# FPGA-Connector.net
KiCad netlist of a schematic drawn in Altium Designer
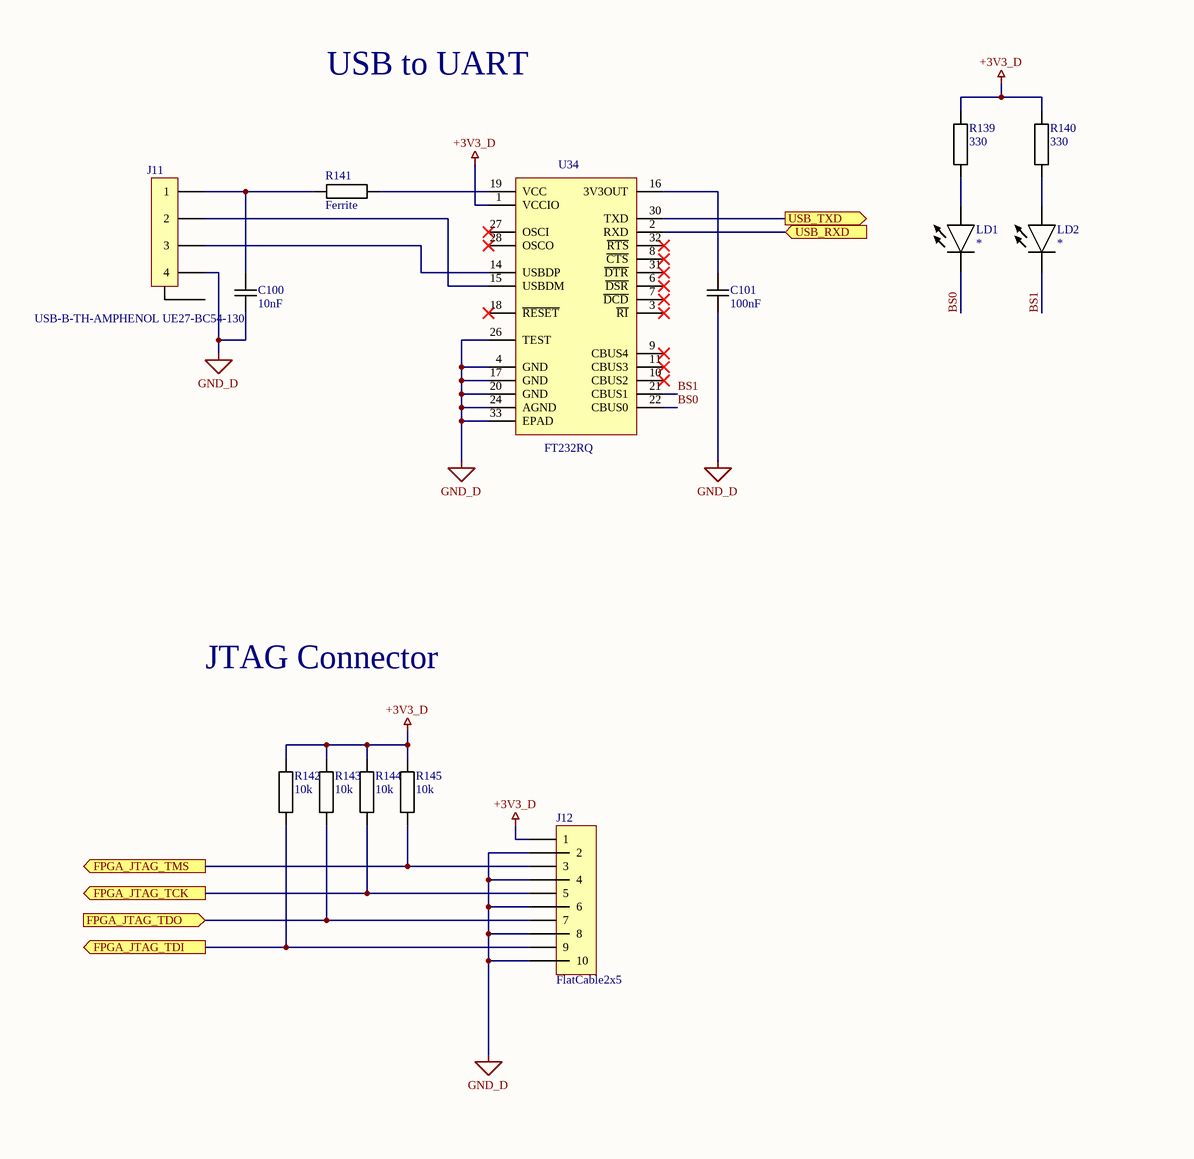
[diagram p0: FPGA-Connector.SchDoc, left]
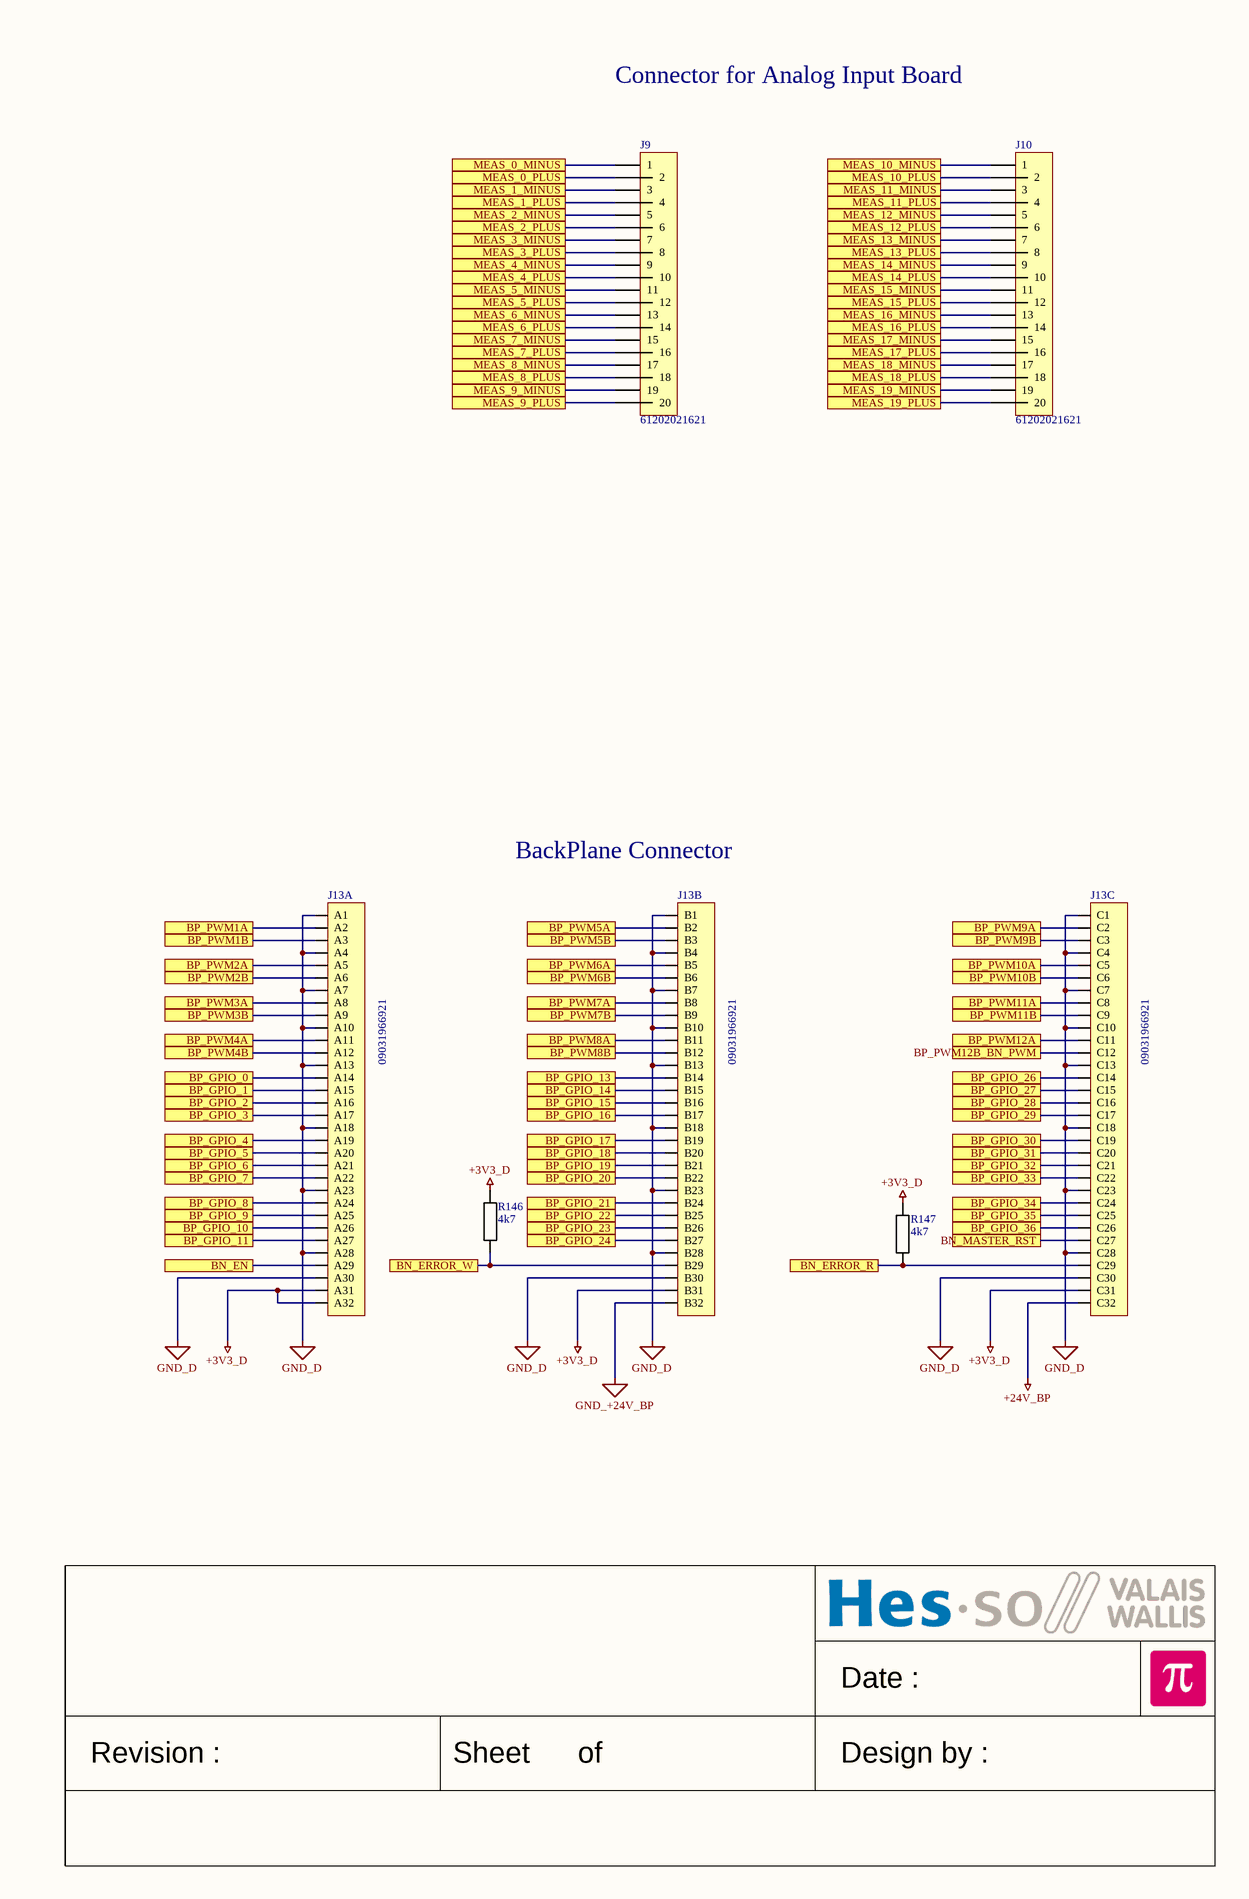
[diagram p1: FPGA-Connector.SchDoc, right]

(export (version "E")
  (design (tool "Eeschema 10.0.6"))
  (components
    (comp (ref "C100")
      (value "10nF")
      (footprint "CAPACITOR 1608 REFLOW")
      (description "Capacitor X7R 10% 50V 1608(0603)")
      (libsource (lib "Capacitor") (part "Capacitor"))
    )
    (comp (ref "C101")
      (value "100nF")
      (footprint "CAPACITOR 1608 REFLOW")
      (description "Capacitor X7R 10% 50V 1608(0603)")
      (libsource (lib "Capacitor") (part "Capacitor"))
    )
    (comp (ref "J9")
      (value "61202021621")
      (footprint "FlatCable2x10 2.54MM Straight TH")
      (description "FlatCable2x10")
      (fields (field (name "MANUFACTURER") "Wurth Elektronik"))
      (libsource (lib "Connector") (part "FlatCable2x10"))
    )
    (comp (ref "J10")
      (value "61202021621")
      (footprint "FlatCable2x10 2.54MM Straight TH")
      (description "FlatCable2x10")
      (fields (field (name "MANUFACTURER") "Wurth Elektronik"))
      (libsource (lib "Connector") (part "FlatCable2x10"))
    )
    (comp (ref "J11")
      (value "USB-B-TH-AMPHENOL UE27-BC54-130")
      (footprint "USB-B TH AMPHENOL UE27-BC54-130")
      (libsource (lib "Connector") (part "USB-B-TH-AMPHENOL UE27-BC54-130"))
    )
    (comp (ref "J12")
      (value "FlatCable2x5")
      (footprint "FlatCable2x5 2MM Straight TH FCI 98414-G06-10ULF")
      (libsource (lib "Connector") (part "FlatCable2x5"))
    )
    (comp (ref "J13")
      (value "09031966921")
      (footprint "DIN41612 MALE 3X32 ABC R90")
      (description "DIN41612 MALE 3X32 ABC R90")
      (fields (field (name "MANUFACTURER") "Harting"))
      (libsource (lib "Connector") (part "DIN41612 MALE 3X32 ABC R90"))
    )
    (comp (ref "LD1")
      (value "*")
      (footprint "LED 1608 REFLOW")
      (description "LED generic")
      (libsource (lib "Diode") (part "LED"))
    )
    (comp (ref "LD2")
      (value "*")
      (footprint "LED 1608 REFLOW")
      (description "LED generic")
      (libsource (lib "Diode") (part "LED"))
    )
    (comp (ref "R139")
      (value "330")
      (footprint "RESISTOR 2012 REFLOW")
      (description "Resistor 1% 50V 125mW 2012(0805)")
      (libsource (lib "Resistor") (part "Resistor"))
    )
    (comp (ref "R140")
      (value "330")
      (footprint "RESISTOR 2012 REFLOW")
      (description "Resistor 1% 50V 125mW 2012(0805)")
      (libsource (lib "Resistor") (part "Resistor"))
    )
    (comp (ref "R141")
      (value "Ferrite")
      (footprint "RESISTOR 1608 REFLOW")
      (description "Resistor 1% 50V 100mW 1608(0603)")
      (libsource (lib "Resistor") (part "Resistor"))
    )
    (comp (ref "R142")
      (value "10k")
      (footprint "RESISTOR 1608 REFLOW")
      (description "Resistor 1% 50V 100mW 1608(0603)")
      (libsource (lib "Resistor") (part "Resistor"))
    )
    (comp (ref "R143")
      (value "10k")
      (footprint "RESISTOR 1608 REFLOW")
      (description "Resistor 1% 50V 100mW 1608(0603)")
      (libsource (lib "Resistor") (part "Resistor"))
    )
    (comp (ref "R144")
      (value "10k")
      (footprint "RESISTOR 1608 REFLOW")
      (description "Resistor 1% 50V 100mW 1608(0603)")
      (libsource (lib "Resistor") (part "Resistor"))
    )
    (comp (ref "R145")
      (value "10k")
      (footprint "RESISTOR 1608 REFLOW")
      (description "Resistor 1% 50V 100mW 1608(0603)")
      (libsource (lib "Resistor") (part "Resistor"))
    )
    (comp (ref "R146")
      (value "4k7")
      (footprint "RESISTOR 1608 REFLOW")
      (description "Resistor 1% 50V 100mW 1608(0603)")
      (libsource (lib "Resistor") (part "Resistor"))
    )
    (comp (ref "R147")
      (value "4k7")
      (footprint "RESISTOR 1608 REFLOW")
      (description "Resistor 1% 50V 100mW 1608(0603)")
      (libsource (lib "Resistor") (part "Resistor"))
    )
    (comp (ref "U34")
      (value "FT232RQ")
      (footprint "QFN32 P0.5 T3.2x3.2 C5.0X5.0 H1.0")
      (description "24-Bit ADC with Ultra Low Noise PGIA - Crystal")
      (libsource (lib "IntegratedCircuit - Copy") (part "FT232RQ"))
    )
  )
  (nets
    (net (code "1") (name "+3V3_D") (class "Default")
      (node (ref "J12") (pin "1") (pinfunction "1_1") (pintype "passive"))
      (node (ref "J13") (pin "A31") (pinfunction "A31_A31") (pintype "passive"))
      (node (ref "J13") (pin "A32") (pinfunction "A32_A32") (pintype "passive"))
      (node (ref "J13") (pin "B31") (pinfunction "B31_B31") (pintype "passive"))
      (node (ref "J13") (pin "C31") (pinfunction "C31_C31") (pintype "passive"))
      (node (ref "R139") (pin "2") (pinfunction "2_2") (pintype "passive"))
      (node (ref "R140") (pin "2") (pinfunction "2_2") (pintype "passive"))
      (node (ref "R142") (pin "2") (pinfunction "2_2") (pintype "passive"))
      (node (ref "R143") (pin "2") (pinfunction "2_2") (pintype "passive"))
      (node (ref "R144") (pin "2") (pinfunction "2_2") (pintype "passive"))
      (node (ref "R145") (pin "2") (pinfunction "2_2") (pintype "passive"))
      (node (ref "R146") (pin "2") (pinfunction "2_2") (pintype "passive"))
      (node (ref "R147") (pin "2") (pinfunction "2_2") (pintype "passive"))
      (node (ref "U34") (pin "1") (pinfunction "VCCIO_1") (pintype "passive"))
    )
    (net (code "2") (name "+24V_BP") (class "Default")
      (node (ref "J13") (pin "C32") (pinfunction "C32_C32") (pintype "passive"))
    )
    (net (code "3") (name "/BN_EN") (class "Default")
      (node (ref "J13") (pin "A29") (pinfunction "A29_A29") (pintype "passive"))
    )
    (net (code "4") (name "/BN_ERROR_R") (class "Default")
      (node (ref "J13") (pin "C29") (pinfunction "C29_C29") (pintype "passive"))
      (node (ref "R147") (pin "1") (pinfunction "1_1") (pintype "passive"))
    )
    (net (code "5") (name "/BN_ERROR_W") (class "Default")
      (node (ref "J13") (pin "B29") (pinfunction "B29_B29") (pintype "passive"))
      (node (ref "R146") (pin "1") (pinfunction "1_1") (pintype "passive"))
    )
    (net (code "6") (name "/BN_MASTER_RST") (class "Default")
      (node (ref "J13") (pin "C27") (pinfunction "C27_C27") (pintype "passive"))
    )
    (net (code "7") (name "/BP_GPIO_0") (class "Default")
      (node (ref "J13") (pin "A14") (pinfunction "A14_A14") (pintype "passive"))
    )
    (net (code "8") (name "/BP_GPIO_1") (class "Default")
      (node (ref "J13") (pin "A15") (pinfunction "A15_A15") (pintype "passive"))
    )
    (net (code "9") (name "/BP_GPIO_2") (class "Default")
      (node (ref "J13") (pin "A16") (pinfunction "A16_A16") (pintype "passive"))
    )
    (net (code "10") (name "/BP_GPIO_3") (class "Default")
      (node (ref "J13") (pin "A17") (pinfunction "A17_A17") (pintype "passive"))
    )
    (net (code "11") (name "/BP_GPIO_4") (class "Default")
      (node (ref "J13") (pin "A19") (pinfunction "A19_A19") (pintype "passive"))
    )
    (net (code "12") (name "/BP_GPIO_5") (class "Default")
      (node (ref "J13") (pin "A20") (pinfunction "A20_A20") (pintype "passive"))
    )
    (net (code "13") (name "/BP_GPIO_6") (class "Default")
      (node (ref "J13") (pin "A21") (pinfunction "A21_A21") (pintype "passive"))
    )
    (net (code "14") (name "/BP_GPIO_7") (class "Default")
      (node (ref "J13") (pin "A22") (pinfunction "A22_A22") (pintype "passive"))
    )
    (net (code "15") (name "/BP_GPIO_8") (class "Default")
      (node (ref "J13") (pin "A24") (pinfunction "A24_A24") (pintype "passive"))
    )
    (net (code "16") (name "/BP_GPIO_9") (class "Default")
      (node (ref "J13") (pin "A25") (pinfunction "A25_A25") (pintype "passive"))
    )
    (net (code "17") (name "/BP_GPIO_10") (class "Default")
      (node (ref "J13") (pin "A26") (pinfunction "A26_A26") (pintype "passive"))
    )
    (net (code "18") (name "/BP_GPIO_11") (class "Default")
      (node (ref "J13") (pin "A27") (pinfunction "A27_A27") (pintype "passive"))
    )
    (net (code "19") (name "/BP_GPIO_13") (class "Default")
      (node (ref "J13") (pin "B14") (pinfunction "B14_B14") (pintype "passive"))
    )
    (net (code "20") (name "/BP_GPIO_14") (class "Default")
      (node (ref "J13") (pin "B15") (pinfunction "B15_B15") (pintype "passive"))
    )
    (net (code "21") (name "/BP_GPIO_15") (class "Default")
      (node (ref "J13") (pin "B16") (pinfunction "B16_B16") (pintype "passive"))
    )
    (net (code "22") (name "/BP_GPIO_16") (class "Default")
      (node (ref "J13") (pin "B17") (pinfunction "B17_B17") (pintype "passive"))
    )
    (net (code "23") (name "/BP_GPIO_17") (class "Default")
      (node (ref "J13") (pin "B19") (pinfunction "B19_B19") (pintype "passive"))
    )
    (net (code "24") (name "/BP_GPIO_18") (class "Default")
      (node (ref "J13") (pin "B20") (pinfunction "B20_B20") (pintype "passive"))
    )
    (net (code "25") (name "/BP_GPIO_19") (class "Default")
      (node (ref "J13") (pin "B21") (pinfunction "B21_B21") (pintype "passive"))
    )
    (net (code "26") (name "/BP_GPIO_20") (class "Default")
      (node (ref "J13") (pin "B22") (pinfunction "B22_B22") (pintype "passive"))
    )
    (net (code "27") (name "/BP_GPIO_21") (class "Default")
      (node (ref "J13") (pin "B24") (pinfunction "B24_B24") (pintype "passive"))
    )
    (net (code "28") (name "/BP_GPIO_22") (class "Default")
      (node (ref "J13") (pin "B25") (pinfunction "B25_B25") (pintype "passive"))
    )
    (net (code "29") (name "/BP_GPIO_23") (class "Default")
      (node (ref "J13") (pin "B26") (pinfunction "B26_B26") (pintype "passive"))
    )
    (net (code "30") (name "/BP_GPIO_24") (class "Default")
      (node (ref "J13") (pin "B27") (pinfunction "B27_B27") (pintype "passive"))
    )
    (net (code "31") (name "/BP_GPIO_26") (class "Default")
      (node (ref "J13") (pin "C14") (pinfunction "C14_C14") (pintype "passive"))
    )
    (net (code "32") (name "/BP_GPIO_27") (class "Default")
      (node (ref "J13") (pin "C15") (pinfunction "C15_C15") (pintype "passive"))
    )
    (net (code "33") (name "/BP_GPIO_28") (class "Default")
      (node (ref "J13") (pin "C16") (pinfunction "C16_C16") (pintype "passive"))
    )
    (net (code "34") (name "/BP_GPIO_29") (class "Default")
      (node (ref "J13") (pin "C17") (pinfunction "C17_C17") (pintype "passive"))
    )
    (net (code "35") (name "/BP_GPIO_30") (class "Default")
      (node (ref "J13") (pin "C19") (pinfunction "C19_C19") (pintype "passive"))
    )
    (net (code "36") (name "/BP_GPIO_31") (class "Default")
      (node (ref "J13") (pin "C20") (pinfunction "C20_C20") (pintype "passive"))
    )
    (net (code "37") (name "/BP_GPIO_32") (class "Default")
      (node (ref "J13") (pin "C21") (pinfunction "C21_C21") (pintype "passive"))
    )
    (net (code "38") (name "/BP_GPIO_33") (class "Default")
      (node (ref "J13") (pin "C22") (pinfunction "C22_C22") (pintype "passive"))
    )
    (net (code "39") (name "/BP_GPIO_34") (class "Default")
      (node (ref "J13") (pin "C24") (pinfunction "C24_C24") (pintype "passive"))
    )
    (net (code "40") (name "/BP_GPIO_35") (class "Default")
      (node (ref "J13") (pin "C25") (pinfunction "C25_C25") (pintype "passive"))
    )
    (net (code "41") (name "/BP_GPIO_36") (class "Default")
      (node (ref "J13") (pin "C26") (pinfunction "C26_C26") (pintype "passive"))
    )
    (net (code "42") (name "/BP_PWM1A") (class "Default")
      (node (ref "J13") (pin "A2") (pinfunction "A2_A2") (pintype "passive"))
    )
    (net (code "43") (name "/BP_PWM1B") (class "Default")
      (node (ref "J13") (pin "A3") (pinfunction "A3_A3") (pintype "passive"))
    )
    (net (code "44") (name "/BP_PWM2A") (class "Default")
      (node (ref "J13") (pin "A5") (pinfunction "A5_A5") (pintype "passive"))
    )
    (net (code "45") (name "/BP_PWM2B") (class "Default")
      (node (ref "J13") (pin "A6") (pinfunction "A6_A6") (pintype "passive"))
    )
    (net (code "46") (name "/BP_PWM3A") (class "Default")
      (node (ref "J13") (pin "A8") (pinfunction "A8_A8") (pintype "passive"))
    )
    (net (code "47") (name "/BP_PWM3B") (class "Default")
      (node (ref "J13") (pin "A9") (pinfunction "A9_A9") (pintype "passive"))
    )
    (net (code "48") (name "/BP_PWM4A") (class "Default")
      (node (ref "J13") (pin "A11") (pinfunction "A11_A11") (pintype "passive"))
    )
    (net (code "49") (name "/BP_PWM4B") (class "Default")
      (node (ref "J13") (pin "A12") (pinfunction "A12_A12") (pintype "passive"))
    )
    (net (code "50") (name "/BP_PWM5A") (class "Default")
      (node (ref "J13") (pin "B2") (pinfunction "B2_B2") (pintype "passive"))
    )
    (net (code "51") (name "/BP_PWM5B") (class "Default")
      (node (ref "J13") (pin "B3") (pinfunction "B3_B3") (pintype "passive"))
    )
    (net (code "52") (name "/BP_PWM6A") (class "Default")
      (node (ref "J13") (pin "B5") (pinfunction "B5_B5") (pintype "passive"))
    )
    (net (code "53") (name "/BP_PWM6B") (class "Default")
      (node (ref "J13") (pin "B6") (pinfunction "B6_B6") (pintype "passive"))
    )
    (net (code "54") (name "/BP_PWM7A") (class "Default")
      (node (ref "J13") (pin "B8") (pinfunction "B8_B8") (pintype "passive"))
    )
    (net (code "55") (name "/BP_PWM7B") (class "Default")
      (node (ref "J13") (pin "B9") (pinfunction "B9_B9") (pintype "passive"))
    )
    (net (code "56") (name "/BP_PWM8A") (class "Default")
      (node (ref "J13") (pin "B11") (pinfunction "B11_B11") (pintype "passive"))
    )
    (net (code "57") (name "/BP_PWM8B") (class "Default")
      (node (ref "J13") (pin "B12") (pinfunction "B12_B12") (pintype "passive"))
    )
    (net (code "58") (name "/BP_PWM9A") (class "Default")
      (node (ref "J13") (pin "C2") (pinfunction "C2_C2") (pintype "passive"))
    )
    (net (code "59") (name "/BP_PWM9B") (class "Default")
      (node (ref "J13") (pin "C3") (pinfunction "C3_C3") (pintype "passive"))
    )
    (net (code "60") (name "/BP_PWM10A") (class "Default")
      (node (ref "J13") (pin "C5") (pinfunction "C5_C5") (pintype "passive"))
    )
    (net (code "61") (name "/BP_PWM10B") (class "Default")
      (node (ref "J13") (pin "C6") (pinfunction "C6_C6") (pintype "passive"))
    )
    (net (code "62") (name "/BP_PWM11A") (class "Default")
      (node (ref "J13") (pin "C8") (pinfunction "C8_C8") (pintype "passive"))
    )
    (net (code "63") (name "/BP_PWM11B") (class "Default")
      (node (ref "J13") (pin "C9") (pinfunction "C9_C9") (pintype "passive"))
    )
    (net (code "64") (name "/BP_PWM12A") (class "Default")
      (node (ref "J13") (pin "C11") (pinfunction "C11_C11") (pintype "passive"))
    )
    (net (code "65") (name "/BP_PWM12B_BN_PWM") (class "Default")
      (node (ref "J13") (pin "C12") (pinfunction "C12_C12") (pintype "passive"))
    )
    (net (code "66") (name "/BS0") (class "Default")
      (node (ref "LD1") (pin "1") (pinfunction "C_1") (pintype "passive"))
      (node (ref "U34") (pin "22") (pinfunction "CBUS0_22") (pintype "passive"))
    )
    (net (code "67") (name "/BS1") (class "Default")
      (node (ref "LD2") (pin "1") (pinfunction "C_1") (pintype "passive"))
      (node (ref "U34") (pin "21") (pinfunction "CBUS1_21") (pintype "passive"))
    )
    (net (code "68") (name "/FPGA_JTAG_TCK") (class "Default")
      (node (ref "J12") (pin "5") (pinfunction "5_5") (pintype "passive"))
      (node (ref "R144") (pin "1") (pinfunction "1_1") (pintype "passive"))
    )
    (net (code "69") (name "/FPGA_JTAG_TDI") (class "Default")
      (node (ref "J12") (pin "9") (pinfunction "9_9") (pintype "passive"))
      (node (ref "R142") (pin "1") (pinfunction "1_1") (pintype "passive"))
    )
    (net (code "70") (name "/FPGA_JTAG_TDO") (class "Default")
      (node (ref "J12") (pin "7") (pinfunction "7_7") (pintype "passive"))
      (node (ref "R143") (pin "1") (pinfunction "1_1") (pintype "passive"))
    )
    (net (code "71") (name "/FPGA_JTAG_TMS") (class "Default")
      (node (ref "J12") (pin "3") (pinfunction "3_3") (pintype "passive"))
      (node (ref "R145") (pin "1") (pinfunction "1_1") (pintype "passive"))
    )
    (net (code "72") (name "/MEAS_0_MINUS") (class "Default")
      (node (ref "J9") (pin "1") (pinfunction "1_1") (pintype "passive"))
    )
    (net (code "73") (name "/MEAS_0_PLUS") (class "Default")
      (node (ref "J9") (pin "2") (pinfunction "2_2") (pintype "passive"))
    )
    (net (code "74") (name "/MEAS_1_MINUS") (class "Default")
      (node (ref "J9") (pin "3") (pinfunction "3_3") (pintype "passive"))
    )
    (net (code "75") (name "/MEAS_1_PLUS") (class "Default")
      (node (ref "J9") (pin "4") (pinfunction "4_4") (pintype "passive"))
    )
    (net (code "76") (name "/MEAS_2_MINUS") (class "Default")
      (node (ref "J9") (pin "5") (pinfunction "5_5") (pintype "passive"))
    )
    (net (code "77") (name "/MEAS_2_PLUS") (class "Default")
      (node (ref "J9") (pin "6") (pinfunction "6_6") (pintype "passive"))
    )
    (net (code "78") (name "/MEAS_3_MINUS") (class "Default")
      (node (ref "J9") (pin "7") (pinfunction "7_7") (pintype "passive"))
    )
    (net (code "79") (name "/MEAS_3_PLUS") (class "Default")
      (node (ref "J9") (pin "8") (pinfunction "8_8") (pintype "passive"))
    )
    (net (code "80") (name "/MEAS_4_MINUS") (class "Default")
      (node (ref "J9") (pin "9") (pinfunction "9_9") (pintype "passive"))
    )
    (net (code "81") (name "/MEAS_4_PLUS") (class "Default")
      (node (ref "J9") (pin "10") (pinfunction "10_10") (pintype "passive"))
    )
    (net (code "82") (name "/MEAS_5_MINUS") (class "Default")
      (node (ref "J9") (pin "11") (pinfunction "11_11") (pintype "passive"))
    )
    (net (code "83") (name "/MEAS_5_PLUS") (class "Default")
      (node (ref "J9") (pin "12") (pinfunction "12_12") (pintype "passive"))
    )
    (net (code "84") (name "/MEAS_6_MINUS") (class "Default")
      (node (ref "J9") (pin "13") (pinfunction "13_13") (pintype "passive"))
    )
    (net (code "85") (name "/MEAS_6_PLUS") (class "Default")
      (node (ref "J9") (pin "14") (pinfunction "14_14") (pintype "passive"))
    )
    (net (code "86") (name "/MEAS_7_MINUS") (class "Default")
      (node (ref "J9") (pin "15") (pinfunction "15_15") (pintype "passive"))
    )
    (net (code "87") (name "/MEAS_7_PLUS") (class "Default")
      (node (ref "J9") (pin "16") (pinfunction "16_16") (pintype "passive"))
    )
    (net (code "88") (name "/MEAS_8_MINUS") (class "Default")
      (node (ref "J9") (pin "17") (pinfunction "17_17") (pintype "passive"))
    )
    (net (code "89") (name "/MEAS_8_PLUS") (class "Default")
      (node (ref "J9") (pin "18") (pinfunction "18_18") (pintype "passive"))
    )
    (net (code "90") (name "/MEAS_9_MINUS") (class "Default")
      (node (ref "J9") (pin "19") (pinfunction "19_19") (pintype "passive"))
    )
    (net (code "91") (name "/MEAS_9_PLUS") (class "Default")
      (node (ref "J9") (pin "20") (pinfunction "20_20") (pintype "passive"))
    )
    (net (code "92") (name "/MEAS_10_MINUS") (class "Default")
      (node (ref "J10") (pin "1") (pinfunction "1_1") (pintype "passive"))
    )
    (net (code "93") (name "/MEAS_10_PLUS") (class "Default")
      (node (ref "J10") (pin "2") (pinfunction "2_2") (pintype "passive"))
    )
    (net (code "94") (name "/MEAS_11_MINUS") (class "Default")
      (node (ref "J10") (pin "3") (pinfunction "3_3") (pintype "passive"))
    )
    (net (code "95") (name "/MEAS_11_PLUS") (class "Default")
      (node (ref "J10") (pin "4") (pinfunction "4_4") (pintype "passive"))
    )
    (net (code "96") (name "/MEAS_12_MINUS") (class "Default")
      (node (ref "J10") (pin "5") (pinfunction "5_5") (pintype "passive"))
    )
    (net (code "97") (name "/MEAS_12_PLUS") (class "Default")
      (node (ref "J10") (pin "6") (pinfunction "6_6") (pintype "passive"))
    )
    (net (code "98") (name "/MEAS_13_MINUS") (class "Default")
      (node (ref "J10") (pin "7") (pinfunction "7_7") (pintype "passive"))
    )
    (net (code "99") (name "/MEAS_13_PLUS") (class "Default")
      (node (ref "J10") (pin "8") (pinfunction "8_8") (pintype "passive"))
    )
    (net (code "100") (name "/MEAS_14_MINUS") (class "Default")
      (node (ref "J10") (pin "9") (pinfunction "9_9") (pintype "passive"))
    )
    (net (code "101") (name "/MEAS_14_PLUS") (class "Default")
      (node (ref "J10") (pin "10") (pinfunction "10_10") (pintype "passive"))
    )
    (net (code "102") (name "/MEAS_15_MINUS") (class "Default")
      (node (ref "J10") (pin "11") (pinfunction "11_11") (pintype "passive"))
    )
    (net (code "103") (name "/MEAS_15_PLUS") (class "Default")
      (node (ref "J10") (pin "12") (pinfunction "12_12") (pintype "passive"))
    )
    (net (code "104") (name "/MEAS_16_MINUS") (class "Default")
      (node (ref "J10") (pin "13") (pinfunction "13_13") (pintype "passive"))
    )
    (net (code "105") (name "/MEAS_16_PLUS") (class "Default")
      (node (ref "J10") (pin "14") (pinfunction "14_14") (pintype "passive"))
    )
    (net (code "106") (name "/MEAS_17_MINUS") (class "Default")
      (node (ref "J10") (pin "15") (pinfunction "15_15") (pintype "passive"))
    )
    (net (code "107") (name "/MEAS_17_PLUS") (class "Default")
      (node (ref "J10") (pin "16") (pinfunction "16_16") (pintype "passive"))
    )
    (net (code "108") (name "/MEAS_18_MINUS") (class "Default")
      (node (ref "J10") (pin "17") (pinfunction "17_17") (pintype "passive"))
    )
    (net (code "109") (name "/MEAS_18_PLUS") (class "Default")
      (node (ref "J10") (pin "18") (pinfunction "18_18") (pintype "passive"))
    )
    (net (code "110") (name "/MEAS_19_MINUS") (class "Default")
      (node (ref "J10") (pin "19") (pinfunction "19_19") (pintype "passive"))
    )
    (net (code "111") (name "/MEAS_19_PLUS") (class "Default")
      (node (ref "J10") (pin "20") (pinfunction "20_20") (pintype "passive"))
    )
    (net (code "112") (name "/USB_RXD") (class "Default")
      (node (ref "U34") (pin "2") (pinfunction "RXD_2") (pintype "passive"))
    )
    (net (code "113") (name "/USB_TXD") (class "Default")
      (node (ref "U34") (pin "30") (pinfunction "TXD_30") (pintype "passive"))
    )
    (net (code "114") (name "GND_+24V_BP") (class "Default")
      (node (ref "J13") (pin "B32") (pinfunction "B32_B32") (pintype "passive"))
    )
    (net (code "115") (name "GND_D") (class "Default")
      (node (ref "C100") (pin "1") (pinfunction "1_1") (pintype "passive"))
      (node (ref "C101") (pin "1") (pinfunction "1_1") (pintype "passive"))
      (node (ref "J11") (pin "4") (pinfunction "4_4") (pintype "passive"))
      (node (ref "J12") (pin "10") (pinfunction "10_10") (pintype "passive"))
      (node (ref "J12") (pin "2") (pinfunction "2_2") (pintype "passive"))
      (node (ref "J12") (pin "4") (pinfunction "4_4") (pintype "passive"))
      (node (ref "J12") (pin "6") (pinfunction "6_6") (pintype "passive"))
      (node (ref "J12") (pin "8") (pinfunction "8_8") (pintype "passive"))
      (node (ref "J13") (pin "A1") (pinfunction "A1_A1") (pintype "passive"))
      (node (ref "J13") (pin "A10") (pinfunction "A10_A10") (pintype "passive"))
      (node (ref "J13") (pin "A13") (pinfunction "A13_A13") (pintype "passive"))
      (node (ref "J13") (pin "A18") (pinfunction "A18_A18") (pintype "passive"))
      (node (ref "J13") (pin "A23") (pinfunction "A23_A23") (pintype "passive"))
      (node (ref "J13") (pin "A28") (pinfunction "A28_A28") (pintype "passive"))
      (node (ref "J13") (pin "A30") (pinfunction "A30_A30") (pintype "passive"))
      (node (ref "J13") (pin "A4") (pinfunction "A4_A4") (pintype "passive"))
      (node (ref "J13") (pin "A7") (pinfunction "A7_A7") (pintype "passive"))
      (node (ref "J13") (pin "B1") (pinfunction "B1_B1") (pintype "passive"))
      (node (ref "J13") (pin "B10") (pinfunction "B10_B10") (pintype "passive"))
      (node (ref "J13") (pin "B13") (pinfunction "B13_B13") (pintype "passive"))
      (node (ref "J13") (pin "B18") (pinfunction "B18_B18") (pintype "passive"))
      (node (ref "J13") (pin "B23") (pinfunction "B23_B23") (pintype "passive"))
      (node (ref "J13") (pin "B28") (pinfunction "B28_B28") (pintype "passive"))
      (node (ref "J13") (pin "B30") (pinfunction "B30_B30") (pintype "passive"))
      (node (ref "J13") (pin "B4") (pinfunction "B4_B4") (pintype "passive"))
      (node (ref "J13") (pin "B7") (pinfunction "B7_B7") (pintype "passive"))
      (node (ref "J13") (pin "C1") (pinfunction "C1_C1") (pintype "passive"))
      (node (ref "J13") (pin "C10") (pinfunction "C10_C10") (pintype "passive"))
      (node (ref "J13") (pin "C13") (pinfunction "C13_C13") (pintype "passive"))
      (node (ref "J13") (pin "C18") (pinfunction "C18_C18") (pintype "passive"))
      (node (ref "J13") (pin "C23") (pinfunction "C23_C23") (pintype "passive"))
      (node (ref "J13") (pin "C28") (pinfunction "C28_C28") (pintype "passive"))
      (node (ref "J13") (pin "C30") (pinfunction "C30_C30") (pintype "passive"))
      (node (ref "J13") (pin "C4") (pinfunction "C4_C4") (pintype "passive"))
      (node (ref "J13") (pin "C7") (pinfunction "C7_C7") (pintype "passive"))
      (node (ref "U34") (pin "17") (pinfunction "GND_17") (pintype "passive"))
      (node (ref "U34") (pin "20") (pinfunction "GND_20") (pintype "passive"))
      (node (ref "U34") (pin "24") (pinfunction "AGND_24") (pintype "passive"))
      (node (ref "U34") (pin "26") (pinfunction "TEST_26") (pintype "passive"))
      (node (ref "U34") (pin "33") (pinfunction "EPAD_33") (pintype "passive"))
      (node (ref "U34") (pin "4") (pinfunction "GND_4") (pintype "passive"))
    )
    (net (code "116") (name "Net-(C100-Pad2)") (class "Default")
      (node (ref "C100") (pin "2") (pinfunction "2_2") (pintype "passive"))
      (node (ref "J11") (pin "1") (pinfunction "1_1") (pintype "passive"))
      (node (ref "R141") (pin "1") (pinfunction "1_1") (pintype "passive"))
    )
    (net (code "117") (name "Net-(J11-Pad5)") (class "Default")
      (node (ref "J11") (pin "5") (pinfunction "5_5") (pintype "passive"))
      (node (ref "J11") (pin "6") (pinfunction "6_6") (pintype "passive"))
    )
    (net (code "118") (name "Net-(LD1-A)") (class "Default")
      (node (ref "LD1") (pin "2") (pinfunction "A_2") (pintype "passive"))
      (node (ref "R139") (pin "1") (pinfunction "1_1") (pintype "passive"))
    )
    (net (code "119") (name "Net-(LD2-A)") (class "Default")
      (node (ref "LD2") (pin "2") (pinfunction "A_2") (pintype "passive"))
      (node (ref "R140") (pin "1") (pinfunction "1_1") (pintype "passive"))
    )
    (net (code "120") (name "Net-(U34-3V3OUT)") (class "Default")
      (node (ref "C101") (pin "2") (pinfunction "2_2") (pintype "passive"))
      (node (ref "U34") (pin "16") (pinfunction "3V3OUT_16") (pintype "passive"))
    )
    (net (code "121") (name "Net-(U34-USBDM)") (class "Default")
      (node (ref "J11") (pin "2") (pinfunction "2_2") (pintype "passive"))
      (node (ref "U34") (pin "15") (pinfunction "USBDM_15") (pintype "passive"))
    )
    (net (code "122") (name "Net-(U34-USBDP)") (class "Default")
      (node (ref "J11") (pin "3") (pinfunction "3_3") (pintype "passive"))
      (node (ref "U34") (pin "14") (pinfunction "USBDP_14") (pintype "passive"))
    )
    (net (code "123") (name "Net-(U34-VCC)") (class "Default")
      (node (ref "R141") (pin "2") (pinfunction "2_2") (pintype "passive"))
      (node (ref "U34") (pin "19") (pinfunction "VCC_19") (pintype "passive"))
    )
    (net (code "124") (name "unconnected-(U34-CBUS2-Pad10)") (class "Default")
      (node (ref "U34") (pin "10") (pinfunction "CBUS2_10") (pintype "passive+no_connect"))
    )
    (net (code "125") (name "unconnected-(U34-CBUS3-Pad11)") (class "Default")
      (node (ref "U34") (pin "11") (pinfunction "CBUS3_11") (pintype "passive+no_connect"))
    )
    (net (code "126") (name "unconnected-(U34-CBUS4-Pad9)") (class "Default")
      (node (ref "U34") (pin "9") (pinfunction "CBUS4_9") (pintype "passive+no_connect"))
    )
    (net (code "127") (name "unconnected-(U34-OSCI-Pad27)") (class "Default")
      (node (ref "U34") (pin "27") (pinfunction "OSCI_27") (pintype "passive+no_connect"))
    )
    (net (code "128") (name "unconnected-(U34-OSCO-Pad28)") (class "Default")
      (node (ref "U34") (pin "28") (pinfunction "OSCO_28") (pintype "passive+no_connect"))
    )
    (net (code "129") (name "unconnected-(U34-Pad5)") (class "Default")
      (node (ref "U34") (pin "5") (pintype "passive"))
    )
    (net (code "130") (name "unconnected-(U34-Pad12)") (class "Default")
      (node (ref "U34") (pin "12") (pintype "passive"))
    )
    (net (code "131") (name "unconnected-(U34-Pad13)") (class "Default")
      (node (ref "U34") (pin "13") (pintype "passive"))
    )
    (net (code "132") (name "unconnected-(U34-Pad23)") (class "Default")
      (node (ref "U34") (pin "23") (pintype "passive"))
    )
    (net (code "133") (name "unconnected-(U34-Pad25)") (class "Default")
      (node (ref "U34") (pin "25") (pintype "passive"))
    )
    (net (code "134") (name "unconnected-(U34-Pad29)") (class "Default")
      (node (ref "U34") (pin "29") (pintype "passive"))
    )
    (net (code "135") (name "unconnected-(U34-~{CTS}-Pad8)") (class "Default")
      (node (ref "U34") (pin "8") (pinfunction "~{CTS}_8") (pintype "passive+no_connect"))
    )
    (net (code "136") (name "unconnected-(U34-~{DCD}-Pad7)") (class "Default")
      (node (ref "U34") (pin "7") (pinfunction "~{DCD}_7") (pintype "passive+no_connect"))
    )
    (net (code "137") (name "unconnected-(U34-~{DSR}-Pad6)") (class "Default")
      (node (ref "U34") (pin "6") (pinfunction "~{DSR}_6") (pintype "passive+no_connect"))
    )
    (net (code "138") (name "unconnected-(U34-~{DTR}-Pad31)") (class "Default")
      (node (ref "U34") (pin "31") (pinfunction "~{DTR}_31") (pintype "passive+no_connect"))
    )
    (net (code "139") (name "unconnected-(U34-~{RESET}-Pad18)") (class "Default")
      (node (ref "U34") (pin "18") (pinfunction "~{RESET}_18") (pintype "passive+no_connect"))
    )
    (net (code "140") (name "unconnected-(U34-~{RI}-Pad3)") (class "Default")
      (node (ref "U34") (pin "3") (pinfunction "~{RI}_3") (pintype "passive+no_connect"))
    )
    (net (code "141") (name "unconnected-(U34-~{RTS}-Pad32)") (class "Default")
      (node (ref "U34") (pin "32") (pinfunction "~{RTS}_32") (pintype "passive+no_connect"))
    )
  )
)
